# SCH_schematicdesign_2025-10-19.net
KiCad netlist of a schematic drawn in EasyEDA
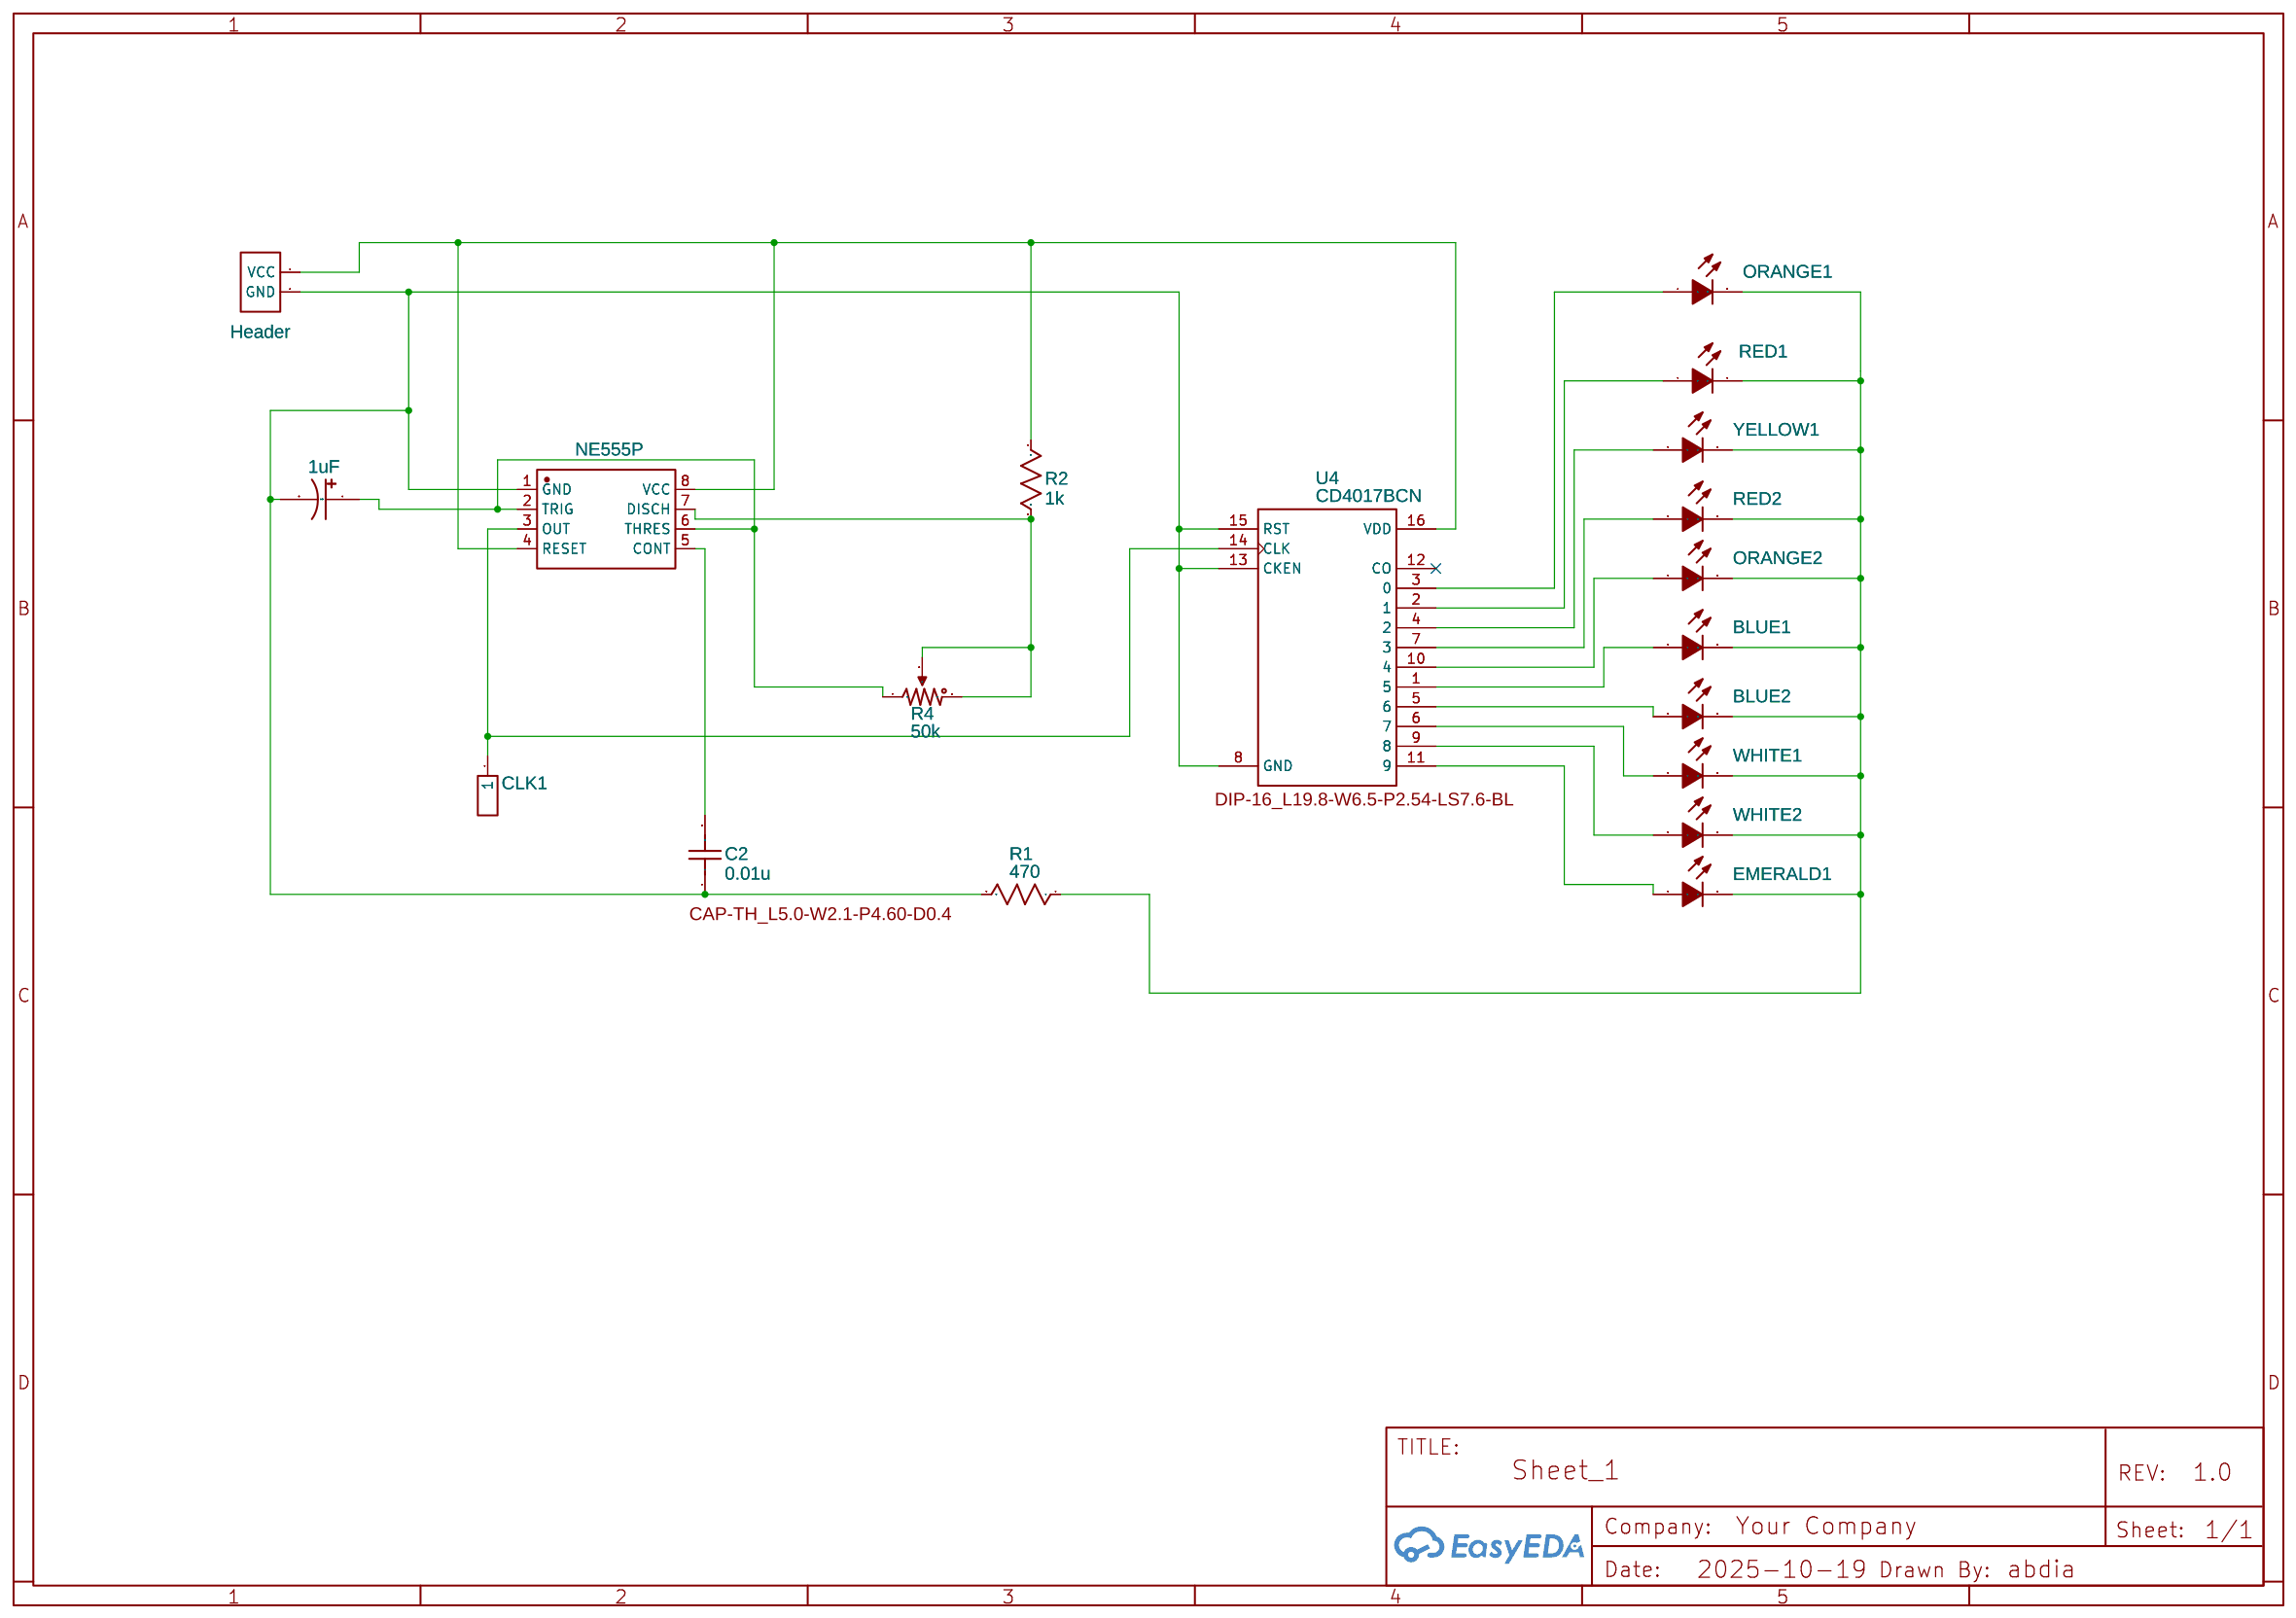
[diagram p0: schematic sheet]

(export (version "E")
  (design (tool "Eeschema 10.0.6"))
  (components
    (comp (ref "BLUE1") (value "LED_5MM") (libsource (lib "") (part "LED_5MM_1")))
    (comp (ref "BLUE2") (value "LED_5MM") (libsource (lib "") (part "LED_5MM_1")))
    (comp (ref "C1")
      (value "1uF")
      (fields (field (name "Manufacturer Part") "UVZ1H010MDD") (field (name "Manufacturer") "Nichicon(尼吉康)"))
      (libsource (lib "") (part "UVZ1H010MDD"))
    )
    (comp (ref "C2") (value "0.01u") (libsource (lib "") (part "C_0603_US")))
    (comp (ref "CLK1")
      (value "C81276")
      (fields
        (field (name "Manufacturer Part") "2.54-1*1P针")
        (field (name "Manufacturer") "BOOMELE(Boom Precision Elec)")
      )
      (libsource (lib "") (part "Header-Male-2.54_1x1"))
    )
    (comp (ref "EMERALD1") (value "LED_5MM") (libsource (lib "") (part "LED_5MM_5")))
    (comp (ref "H1") (value "Header") (libsource (lib "") (part "HEADER-FEMALE-2.54_1X2")))
    (comp (ref "ORANGE1") (value "LED_5MM") (libsource (lib "") (part "LED_5MM_4")))
    (comp (ref "ORANGE2") (value "LED_5MM") (libsource (lib "") (part "LED_5MM_4")))
    (comp (ref "R1")
      (value "470")
      (fields (field (name "Manufacturer Part") "?"))
      (libsource (lib "") (part "Resistor_1"))
    )
    (comp (ref "R2")
      (value "1k")
      (fields (field (name "Manufacturer Part") "?"))
      (libsource (lib "") (part "Resistor"))
    )
    (comp (ref "R4")
      (value "50k")
      (fields (field (name "Manufacturer Part") "?"))
      (libsource (lib "") (part "Potentiometer"))
    )
    (comp (ref "RED1") (value "LED_5MM") (libsource (lib "") (part "LED_5MM")))
    (comp (ref "RED2") (value "LED_5MM") (libsource (lib "") (part "LED_5MM")))
    (comp (ref "U2")
      (value "NE555P")
      (fields (field (name "Manufacturer") "TI(德州仪器)"))
      (libsource (lib "") (part "NE555P"))
    )
    (comp (ref "U4") (value "CD4017BCN") (libsource (lib "") (part "CD4017BCN")))
    (comp (ref "WHITE1") (value "LED_5MM") (libsource (lib "") (part "LED_5MM_2")))
    (comp (ref "WHITE2") (value "LED_5MM") (libsource (lib "") (part "LED_5MM_2")))
    (comp (ref "YELLOW1") (value "LED_5MM") (libsource (lib "") (part "LED_5MM_3")))
  )
  (nets
    (net (code "1") (name "Net-(BLUE1-A)") (class "Default")
      (node (ref "BLUE1") (pin "1") (pinfunction "A_1") (pintype "input"))
      (node (ref "U4") (pin "1") (pinfunction "5_1") (pintype "output"))
    )
    (net (code "2") (name "Net-(BLUE1-K)") (class "Default")
      (node (ref "BLUE1") (pin "2") (pinfunction "K_2") (pintype "input"))
      (node (ref "BLUE2") (pin "2") (pinfunction "K_2") (pintype "input"))
      (node (ref "EMERALD1") (pin "2") (pinfunction "K_2") (pintype "input"))
      (node (ref "ORANGE1") (pin "2") (pinfunction "K_2") (pintype "input"))
      (node (ref "ORANGE2") (pin "2") (pinfunction "K_2") (pintype "input"))
      (node (ref "R1") (pin "1") (pinfunction "1_1") (pintype "unspecified"))
      (node (ref "RED1") (pin "2") (pinfunction "K_2") (pintype "input"))
      (node (ref "RED2") (pin "2") (pinfunction "K_2") (pintype "input"))
      (node (ref "WHITE1") (pin "2") (pinfunction "K_2") (pintype "input"))
      (node (ref "WHITE2") (pin "2") (pinfunction "K_2") (pintype "input"))
      (node (ref "YELLOW1") (pin "2") (pinfunction "K_2") (pintype "input"))
    )
    (net (code "3") (name "Net-(BLUE2-A)") (class "Default")
      (node (ref "BLUE2") (pin "1") (pinfunction "A_1") (pintype "input"))
      (node (ref "U4") (pin "5") (pinfunction "6_5") (pintype "output"))
    )
    (net (code "4") (name "Net-(EMERALD1-A)") (class "Default")
      (node (ref "EMERALD1") (pin "1") (pinfunction "A_1") (pintype "input"))
      (node (ref "U4") (pin "11") (pinfunction "9_11") (pintype "output"))
    )
    (net (code "5") (name "Net-(H1-GND)") (class "Default")
      (node (ref "C1") (pin "2") (pinfunction "2_2") (pintype "unspecified"))
      (node (ref "C2") (pin "1") (pinfunction "1_1") (pintype "unspecified"))
      (node (ref "H1") (pin "2") (pinfunction "GND_2") (pintype "unspecified"))
      (node (ref "R1") (pin "2") (pinfunction "2_2") (pintype "unspecified"))
      (node (ref "U2") (pin "1") (pinfunction "GND_1") (pintype "unspecified"))
      (node (ref "U4") (pin "13") (pinfunction "CKEN_13") (pintype "unspecified"))
      (node (ref "U4") (pin "15") (pinfunction "RST_15") (pintype "unspecified"))
      (node (ref "U4") (pin "8") (pinfunction "GND_8") (pintype "passive"))
    )
    (net (code "6") (name "Net-(H1-VCC)") (class "Default")
      (node (ref "H1") (pin "1") (pinfunction "VCC_1") (pintype "unspecified"))
      (node (ref "R2") (pin "1") (pinfunction "1_1") (pintype "unspecified"))
      (node (ref "U2") (pin "4") (pinfunction "RESET_4") (pintype "unspecified"))
      (node (ref "U2") (pin "8") (pinfunction "VCC_8") (pintype "unspecified"))
      (node (ref "U4") (pin "16") (pinfunction "VDD_16") (pintype "passive"))
    )
    (net (code "7") (name "Net-(ORANGE1-A)") (class "Default")
      (node (ref "ORANGE1") (pin "1") (pinfunction "A_1") (pintype "input"))
      (node (ref "U4") (pin "3") (pinfunction "0_3") (pintype "output"))
    )
    (net (code "8") (name "Net-(ORANGE2-A)") (class "Default")
      (node (ref "ORANGE2") (pin "1") (pinfunction "A_1") (pintype "input"))
      (node (ref "U4") (pin "10") (pinfunction "4_10") (pintype "output"))
    )
    (net (code "9") (name "Net-(R4-2)") (class "Default")
      (node (ref "R2") (pin "2") (pinfunction "2_2") (pintype "unspecified"))
      (node (ref "R4") (pin "2") (pinfunction "3_2") (pintype "unspecified"))
      (node (ref "R4") (pin "3") (pinfunction "2_3") (pintype "unspecified"))
      (node (ref "U2") (pin "7") (pinfunction "DISCH_7") (pintype "unspecified"))
    )
    (net (code "10") (name "Net-(RED1-A)") (class "Default")
      (node (ref "RED1") (pin "1") (pinfunction "A_1") (pintype "input"))
      (node (ref "U4") (pin "2") (pinfunction "1_2") (pintype "output"))
    )
    (net (code "11") (name "Net-(RED2-A)") (class "Default")
      (node (ref "RED2") (pin "1") (pinfunction "A_1") (pintype "input"))
      (node (ref "U4") (pin "7") (pinfunction "3_7") (pintype "output"))
    )
    (net (code "12") (name "Net-(U2-CONT)") (class "Default")
      (node (ref "C2") (pin "2") (pinfunction "2_2") (pintype "unspecified"))
      (node (ref "U2") (pin "5") (pinfunction "CONT_5") (pintype "unspecified"))
    )
    (net (code "13") (name "Net-(U2-OUT)") (class "Default")
      (node (ref "CLK1") (pin "1") (pinfunction "1_1") (pintype "unspecified"))
      (node (ref "U2") (pin "3") (pinfunction "OUT_3") (pintype "unspecified"))
      (node (ref "U4") (pin "14") (pinfunction "CLK_14") (pintype "unspecified"))
    )
    (net (code "14") (name "Net-(U2-THRES)") (class "Default")
      (node (ref "C1") (pin "1") (pinfunction "1_1") (pintype "unspecified"))
      (node (ref "R4") (pin "1") (pinfunction "1_1") (pintype "unspecified"))
      (node (ref "U2") (pin "2") (pinfunction "TRIG_2") (pintype "unspecified"))
      (node (ref "U2") (pin "6") (pinfunction "THRES_6") (pintype "unspecified"))
    )
    (net (code "15") (name "Net-(U4-2)") (class "Default")
      (node (ref "U4") (pin "4") (pinfunction "2_4") (pintype "output"))
      (node (ref "YELLOW1") (pin "1") (pinfunction "A_1") (pintype "input"))
    )
    (net (code "16") (name "Net-(U4-7)") (class "Default")
      (node (ref "U4") (pin "6") (pinfunction "7_6") (pintype "output"))
      (node (ref "WHITE1") (pin "1") (pinfunction "A_1") (pintype "input"))
    )
    (net (code "17") (name "Net-(U4-8)") (class "Default")
      (node (ref "U4") (pin "9") (pinfunction "8_9") (pintype "output"))
      (node (ref "WHITE2") (pin "1") (pinfunction "A_1") (pintype "input"))
    )
    (net (code "18") (name "unconnected-(U4-CO-Pad12)") (class "Default")
      (node (ref "U4") (pin "12") (pinfunction "CO_12") (pintype "output+no_connect"))
    )
  )
)
